# yBrainA1-11March2015.net
KiCad netlist of a schematic drawn in EAGLE
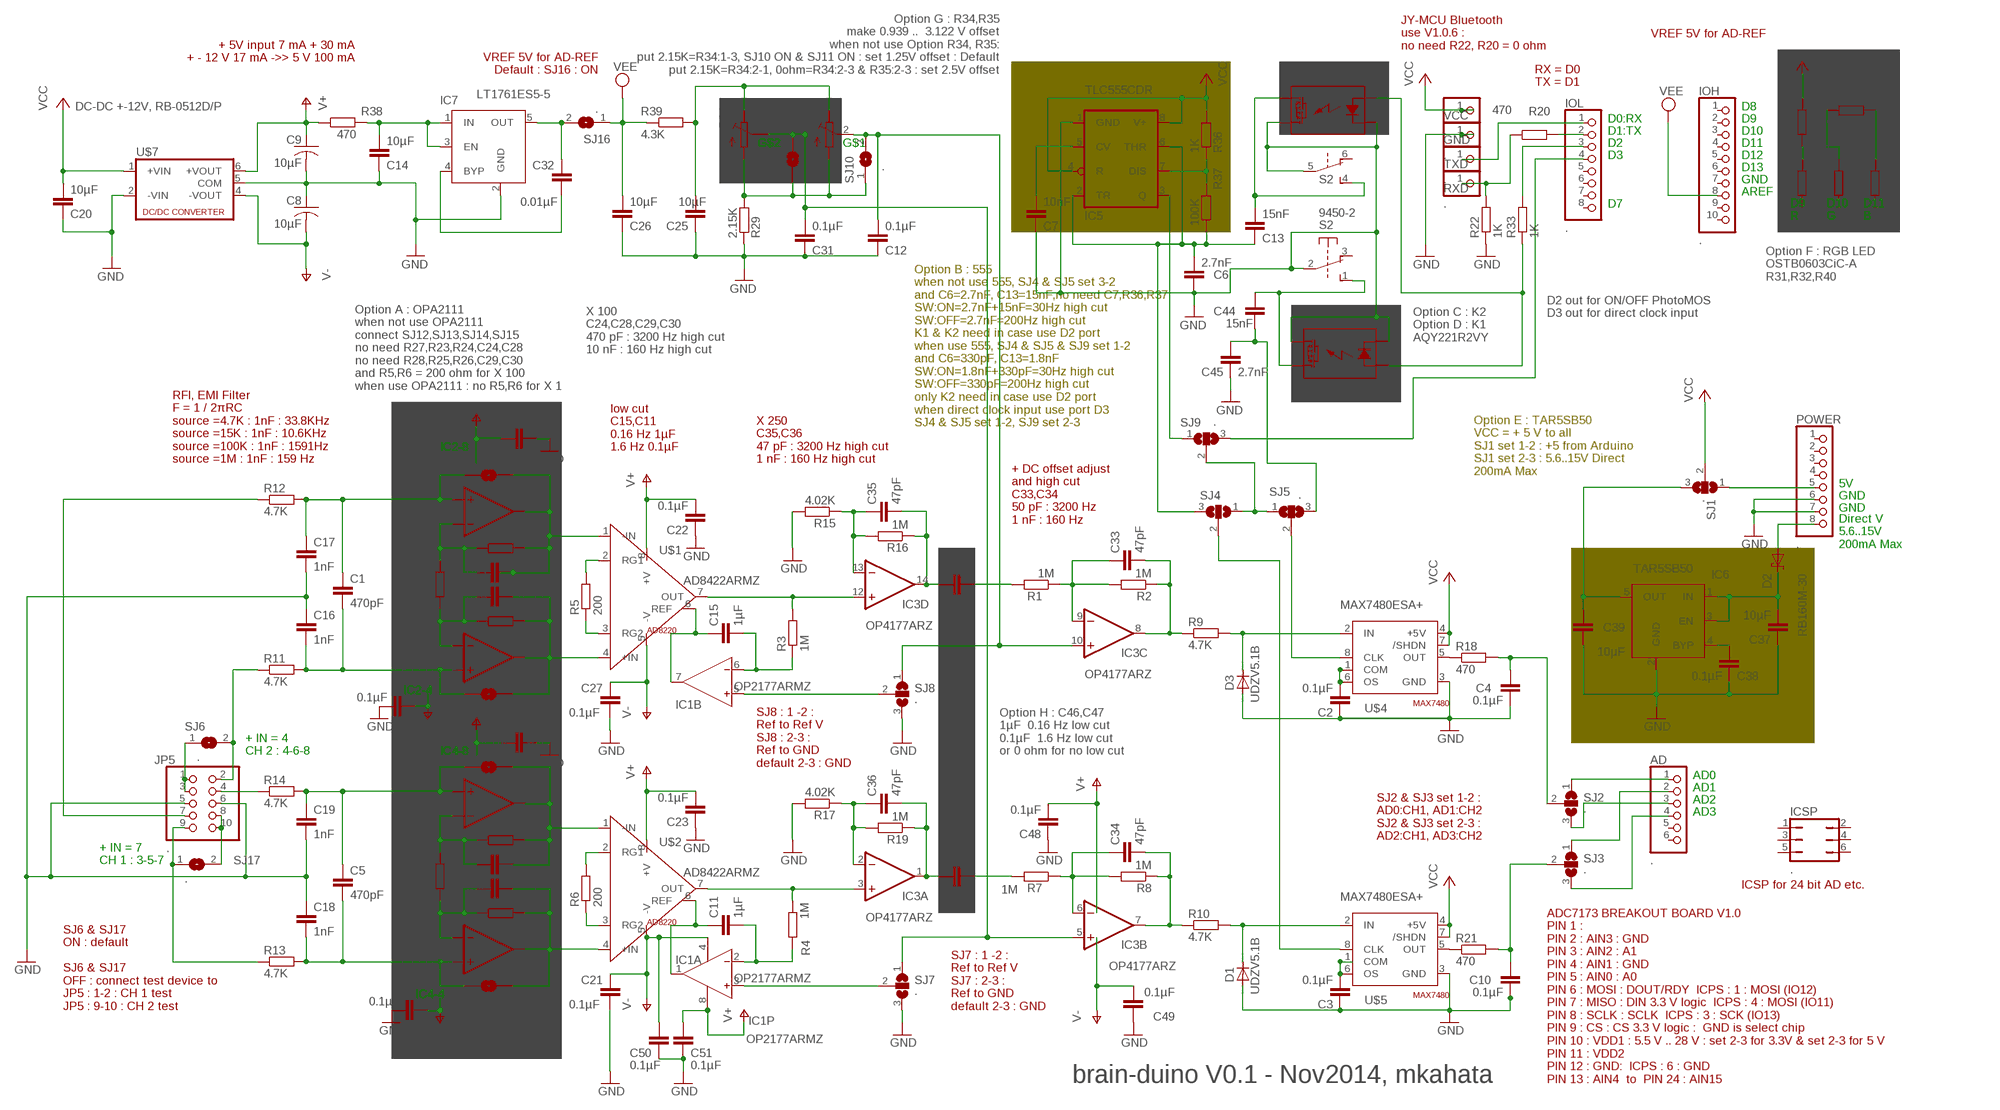
[diagram p0: schematic, sheet 1]

(export (version "E")
  (design (tool "Eeschema 10.0.6"))
  (components
    (comp (ref "AD")
      (value ".")
      (footprint "eagle-import:1X06")
      (libsource (lib "eagle-import") (part "PINHD-1X6"))
    )
    (comp (ref "C1")
      (value "470pF")
      (footprint "eagle-import:C0805")
      (libsource (lib "eagle-import") (part "C-EUC0805"))
    )
    (comp (ref "C2")
      (value "0.1µF")
      (footprint "eagle-import:C0805")
      (libsource (lib "eagle-import") (part "C-EUC0805"))
    )
    (comp (ref "C3")
      (value "0.1µF")
      (footprint "eagle-import:C0805")
      (libsource (lib "eagle-import") (part "C-EUC0805"))
    )
    (comp (ref "C4")
      (value "0.1µF")
      (footprint "eagle-import:C0805")
      (libsource (lib "eagle-import") (part "C-EUC0805"))
    )
    (comp (ref "C5")
      (value "470pF")
      (footprint "eagle-import:C0805")
      (libsource (lib "eagle-import") (part "C-EUC0805"))
    )
    (comp (ref "C6")
      (value "2.7nF")
      (footprint "eagle-import:C0805")
      (libsource (lib "eagle-import") (part "C-EUC0805"))
    )
    (comp (ref "C7")
      (value "10nF")
      (footprint "eagle-import:C0805")
      (libsource (lib "eagle-import") (part "C-EUC0805"))
    )
    (comp (ref "C8")
      (value "10µF")
      (footprint "eagle-import:C0805")
      (libsource (lib "eagle-import") (part "C-USC0805"))
    )
    (comp (ref "C9")
      (value "10µF")
      (footprint "eagle-import:C0805")
      (libsource (lib "eagle-import") (part "C-USC0805"))
    )
    (comp (ref "C10")
      (value "0.1µF")
      (footprint "eagle-import:C0805")
      (libsource (lib "eagle-import") (part "C-EUC0805"))
    )
    (comp (ref "C11")
      (value "1µF")
      (footprint "eagle-import:C0805")
      (libsource (lib "eagle-import") (part "C-EUC0805"))
    )
    (comp (ref "C12")
      (value "0.1µF")
      (footprint "eagle-import:C0805")
      (libsource (lib "eagle-import") (part "C-EUC0805"))
    )
    (comp (ref "C13")
      (value "15nF")
      (footprint "eagle-import:C0805")
      (libsource (lib "eagle-import") (part "C-EUC0805"))
    )
    (comp (ref "C14")
      (value "10µF")
      (footprint "eagle-import:C0805")
      (libsource (lib "eagle-import") (part "C-EUC0805"))
    )
    (comp (ref "C15")
      (value "1µF")
      (footprint "eagle-import:C0805")
      (libsource (lib "eagle-import") (part "C-EUC0805"))
    )
    (comp (ref "C16")
      (value "1nF")
      (footprint "eagle-import:C0805")
      (libsource (lib "eagle-import") (part "C-EUC0805"))
    )
    (comp (ref "C17")
      (value "1nF")
      (footprint "eagle-import:C0805")
      (libsource (lib "eagle-import") (part "C-EUC0805"))
    )
    (comp (ref "C18")
      (value "1nF")
      (footprint "eagle-import:C0805")
      (libsource (lib "eagle-import") (part "C-EUC0805"))
    )
    (comp (ref "C19")
      (value "1nF")
      (footprint "eagle-import:C0805")
      (libsource (lib "eagle-import") (part "C-EUC0805"))
    )
    (comp (ref "C20")
      (value "10µF")
      (footprint "eagle-import:C0805")
      (libsource (lib "eagle-import") (part "C-EUC0805"))
    )
    (comp (ref "C21")
      (value "0.1µF")
      (footprint "eagle-import:C0805")
      (libsource (lib "eagle-import") (part "C-EUC0805"))
    )
    (comp (ref "C22")
      (value "0.1µF")
      (footprint "eagle-import:C0805")
      (libsource (lib "eagle-import") (part "C-EUC0805"))
    )
    (comp (ref "C23")
      (value "0.1µF")
      (footprint "eagle-import:C0805")
      (libsource (lib "eagle-import") (part "C-EUC0805"))
    )
    (comp (ref "C24")
      (value "470pF")
      (footprint "eagle-import:C0805")
      (libsource (lib "eagle-import") (part "C-EUC0805"))
    )
    (comp (ref "C25")
      (value "10µF")
      (footprint "eagle-import:C0805")
      (libsource (lib "eagle-import") (part "C-EUC0805"))
    )
    (comp (ref "C26")
      (value "10µF")
      (footprint "eagle-import:C0805")
      (libsource (lib "eagle-import") (part "C-EUC0805"))
    )
    (comp (ref "C27")
      (value "0.1µF")
      (footprint "eagle-import:C0805")
      (libsource (lib "eagle-import") (part "C-EUC0805"))
    )
    (comp (ref "C28")
      (value "470pF")
      (footprint "eagle-import:C0805")
      (libsource (lib "eagle-import") (part "C-EUC0805"))
    )
    (comp (ref "C29")
      (value "470pF")
      (footprint "eagle-import:C0805")
      (libsource (lib "eagle-import") (part "C-EUC0805"))
    )
    (comp (ref "C30")
      (value "470pF")
      (footprint "eagle-import:C0805")
      (libsource (lib "eagle-import") (part "C-EUC0805"))
    )
    (comp (ref "C31")
      (value "0.1µF")
      (footprint "eagle-import:C0805")
      (libsource (lib "eagle-import") (part "C-EUC0805"))
    )
    (comp (ref "C32")
      (value "0.01µF")
      (footprint "eagle-import:C0805")
      (libsource (lib "eagle-import") (part "C-EUC0805"))
    )
    (comp (ref "C33")
      (value "47pF")
      (footprint "eagle-import:C0805")
      (libsource (lib "eagle-import") (part "C-EUC0805"))
    )
    (comp (ref "C34")
      (value "47pF")
      (footprint "eagle-import:C0805")
      (libsource (lib "eagle-import") (part "C-EUC0805"))
    )
    (comp (ref "C35")
      (value "47pF")
      (footprint "eagle-import:C0805")
      (libsource (lib "eagle-import") (part "C-EUC0805"))
    )
    (comp (ref "C36")
      (value "47pF")
      (footprint "eagle-import:C0805")
      (libsource (lib "eagle-import") (part "C-EUC0805"))
    )
    (comp (ref "C37")
      (value "10µF")
      (footprint "eagle-import:C0805")
      (libsource (lib "eagle-import") (part "C-EUC0805"))
    )
    (comp (ref "C38")
      (value "0.1µF")
      (footprint "eagle-import:C0805")
      (libsource (lib "eagle-import") (part "C-EUC0805"))
    )
    (comp (ref "C39")
      (value "10µF")
      (footprint "eagle-import:C0805")
      (libsource (lib "eagle-import") (part "C-EUC0805"))
    )
    (comp (ref "C40")
      (value "0.1µF")
      (footprint "eagle-import:C0805")
      (libsource (lib "eagle-import") (part "C-EUC0805"))
    )
    (comp (ref "C41")
      (value "0.1µF")
      (footprint "eagle-import:C0805")
      (libsource (lib "eagle-import") (part "C-EUC0805"))
    )
    (comp (ref "C42")
      (value "0.1µF")
      (footprint "eagle-import:C0805")
      (libsource (lib "eagle-import") (part "C-EUC0805"))
    )
    (comp (ref "C43")
      (value "0.1µF")
      (footprint "eagle-import:C0805")
      (libsource (lib "eagle-import") (part "C-EUC0805"))
    )
    (comp (ref "C44")
      (value "15nF")
      (footprint "eagle-import:C0805")
      (libsource (lib "eagle-import") (part "C-EUC0805"))
    )
    (comp (ref "C45")
      (value "2.7nF")
      (footprint "eagle-import:C0805")
      (libsource (lib "eagle-import") (part "C-EUC0805"))
    )
    (comp (ref "C46")
      (value "1µF")
      (footprint "eagle-import:C0805")
      (libsource (lib "eagle-import") (part "C-EUC0805"))
    )
    (comp (ref "C47")
      (value "1µF")
      (footprint "eagle-import:C0805")
      (libsource (lib "eagle-import") (part "C-EUC0805"))
    )
    (comp (ref "C48")
      (value "0.1µF")
      (footprint "eagle-import:C0805")
      (libsource (lib "eagle-import") (part "C-EUC0805"))
    )
    (comp (ref "C49")
      (value "0.1µF")
      (footprint "eagle-import:C0805")
      (libsource (lib "eagle-import") (part "C-EUC0805"))
    )
    (comp (ref "C50")
      (value "0.1µF")
      (footprint "eagle-import:C0805")
      (libsource (lib "eagle-import") (part "C-EUC0805"))
    )
    (comp (ref "C51")
      (value "0.1µF")
      (footprint "eagle-import:C0805")
      (libsource (lib "eagle-import") (part "C-EUC0805"))
    )
    (comp (ref "D1")
      (value "UDZV5.1B")
      (footprint "eagle-import:SOD110-R")
      (libsource (lib "eagle-import") (part "DIODE-SOD110-R"))
    )
    (comp (ref "D2")
      (value "RB160M-30")
      (footprint "eagle-import:POWERDI323")
      (libsource (lib "eagle-import") (part "PD3S160"))
    )
    (comp (ref "D3")
      (value "UDZV5.1B")
      (footprint "eagle-import:SOD110-R")
      (libsource (lib "eagle-import") (part "DIODE-SOD110-R"))
    )
    (comp (ref "GND")
      (value ".")
      (footprint "eagle-import:1X01")
      (libsource (lib "eagle-import") (part "PINHD-1X1"))
    )
    (comp (ref "IC1")
      (value "OP2177ARMZ")
      (footprint "eagle-import:MSOP08")
      (fields (field (name "MPN") "AD8656ARMZ"))
      (libsource (lib "eagle-import") (part "AD8656RM"))
    )
    (comp (ref "IC2")
      (value "OPA2111KP")
      (footprint "eagle-import:DIL08")
      (libsource (lib "eagle-import") (part "OPA2111P"))
    )
    (comp (ref "IC3")
      (value "OP4177ARZ")
      (footprint "eagle-import:SO14")
      (libsource (lib "eagle-import") (part "TL064D"))
    )
    (comp (ref "IC4")
      (value "OPA2111KP")
      (footprint "eagle-import:DIL08")
      (libsource (lib "eagle-import") (part "OPA2111P"))
    )
    (comp (ref "IC5")
      (value "TLC555CDR")
      (footprint "eagle-import:SO08")
      (libsource (lib "eagle-import") (part "555DLM"))
    )
    (comp (ref "IC6")
      (value "TAR5SB50")
      (footprint "eagle-import:SOT23-5")
      (libsource (lib "eagle-import") (part "MIC5219XX"))
    )
    (comp (ref "IC7")
      (value "LT1761ES5-5")
      (footprint "eagle-import:SOT23-5")
      (libsource (lib "eagle-import") (part "MIC5219XX"))
    )
    (comp (ref "ICSP")
      (value ".")
      (footprint "eagle-import:JP3Q")
      (libsource (lib "eagle-import") (part "JP3Q"))
    )
    (comp (ref "IOH")
      (value ".")
      (footprint "eagle-import:1X10")
      (libsource (lib "eagle-import") (part "PINHD-1X10"))
    )
    (comp (ref "IOL")
      (value ".")
      (footprint "eagle-import:1X08")
      (libsource (lib "eagle-import") (part "PINHD-1X8"))
    )
    (comp (ref "JP5")
      (value ".")
      (footprint "eagle-import:2X05_90")
      (libsource (lib "eagle-import") (part "PINHD-2X5/90"))
    )
    (comp (ref "K1")
      (value "AQY221R2VY")
      (footprint "eagle-import:SSOP4")
      (fields (field (name "MF") "AROMAT/ MATSUSHITA") (field (name "MPN") "AQY221R2V"))
      (libsource (lib "eagle-import") (part "AQY2212VR"))
    )
    (comp (ref "K2")
      (value "AQY221R2VY")
      (footprint "eagle-import:SSOP4")
      (fields (field (name "MF") "AROMAT/ MATSUSHITA") (field (name "MPN") "AQY221R2V"))
      (libsource (lib "eagle-import") (part "AQY2212VR"))
    )
    (comp (ref "POWER")
      (value ".")
      (footprint "eagle-import:1X08")
      (libsource (lib "eagle-import") (part "PINHD-1X8"))
    )
    (comp (ref "R1")
      (value "1M")
      (footprint "eagle-import:R0805")
      (libsource (lib "eagle-import") (part "R-EU_R0805"))
    )
    (comp (ref "R2")
      (value "1M")
      (footprint "eagle-import:R0805")
      (libsource (lib "eagle-import") (part "R-EU_R0805"))
    )
    (comp (ref "R3")
      (value "1M")
      (footprint "eagle-import:R0805")
      (libsource (lib "eagle-import") (part "R-EU_R0805"))
    )
    (comp (ref "R4")
      (value "1M")
      (footprint "eagle-import:R0805")
      (libsource (lib "eagle-import") (part "R-EU_R0805"))
    )
    (comp (ref "R5")
      (value "200")
      (footprint "eagle-import:R0805")
      (libsource (lib "eagle-import") (part "R-EU_R0805"))
    )
    (comp (ref "R6")
      (value "200")
      (footprint "eagle-import:R0805")
      (libsource (lib "eagle-import") (part "R-EU_R0805"))
    )
    (comp (ref "R7")
      (value "1M")
      (footprint "eagle-import:R0805")
      (libsource (lib "eagle-import") (part "R-EU_R0805"))
    )
    (comp (ref "R8")
      (value "1M")
      (footprint "eagle-import:R0805")
      (libsource (lib "eagle-import") (part "R-EU_R0805"))
    )
    (comp (ref "R9")
      (value "4.7K")
      (footprint "eagle-import:R0805")
      (libsource (lib "eagle-import") (part "R-EU_R0805"))
    )
    (comp (ref "R10")
      (value "4.7K")
      (footprint "eagle-import:R0805")
      (libsource (lib "eagle-import") (part "R-EU_R0805"))
    )
    (comp (ref "R11")
      (value "4.7K")
      (footprint "eagle-import:R0805")
      (libsource (lib "eagle-import") (part "R-EU_R0805"))
    )
    (comp (ref "R12")
      (value "4.7K")
      (footprint "eagle-import:R0805")
      (libsource (lib "eagle-import") (part "R-EU_R0805"))
    )
    (comp (ref "R13")
      (value "4.7K")
      (footprint "eagle-import:R0805")
      (libsource (lib "eagle-import") (part "R-EU_R0805"))
    )
    (comp (ref "R14")
      (value "4.7K")
      (footprint "eagle-import:R0805")
      (libsource (lib "eagle-import") (part "R-EU_R0805"))
    )
    (comp (ref "R15")
      (value "4.02K")
      (footprint "eagle-import:R0805")
      (libsource (lib "eagle-import") (part "R-EU_R0805"))
    )
    (comp (ref "R16")
      (value "1M")
      (footprint "eagle-import:R0805")
      (libsource (lib "eagle-import") (part "R-EU_R0805"))
    )
    (comp (ref "R17")
      (value "4.02K")
      (footprint "eagle-import:R0805")
      (libsource (lib "eagle-import") (part "R-EU_R0805"))
    )
    (comp (ref "R18")
      (value "470")
      (footprint "eagle-import:R0805")
      (libsource (lib "eagle-import") (part "R-EU_R0805"))
    )
    (comp (ref "R19")
      (value "1M")
      (footprint "eagle-import:R0805")
      (libsource (lib "eagle-import") (part "R-EU_R0805"))
    )
    (comp (ref "R20")
      (value "470")
      (footprint "eagle-import:R0805")
      (libsource (lib "eagle-import") (part "R-EU_R0805"))
    )
    (comp (ref "R21")
      (value "470")
      (footprint "eagle-import:R0805")
      (libsource (lib "eagle-import") (part "R-EU_R0805"))
    )
    (comp (ref "R22")
      (value "1K")
      (footprint "eagle-import:R0805")
      (libsource (lib "eagle-import") (part "R-EU_R0805"))
    )
    (comp (ref "R23")
      (value "100K")
      (footprint "eagle-import:R0805")
      (libsource (lib "eagle-import") (part "R-EU_R0805"))
    )
    (comp (ref "R24")
      (value "100K")
      (footprint "eagle-import:R0805")
      (libsource (lib "eagle-import") (part "R-EU_R0805"))
    )
    (comp (ref "R25")
      (value "100K")
      (footprint "eagle-import:R0805")
      (libsource (lib "eagle-import") (part "R-EU_R0805"))
    )
    (comp (ref "R26")
      (value "100K")
      (footprint "eagle-import:R0805")
      (libsource (lib "eagle-import") (part "R-EU_R0805"))
    )
    (comp (ref "R27")
      (value "2K")
      (footprint "eagle-import:R0805")
      (libsource (lib "eagle-import") (part "R-EU_R0805"))
    )
    (comp (ref "R28")
      (value "2K")
      (footprint "eagle-import:R0805")
      (libsource (lib "eagle-import") (part "R-EU_R0805"))
    )
    (comp (ref "R29")
      (value "2.15K")
      (footprint "eagle-import:R0805")
      (libsource (lib "eagle-import") (part "R-EU_R0805"))
    )
    (comp (ref "R30")
      (value "LED")
      (footprint "eagle-import:R0402")
      (libsource (lib "eagle-import") (part "R-EU_R0402"))
    )
    (comp (ref "R31")
      (value "1K")
      (footprint "eagle-import:R0402")
      (libsource (lib "eagle-import") (part "R-EU_R0402"))
    )
    (comp (ref "R32")
      (value "1K")
      (footprint "eagle-import:R0402")
      (libsource (lib "eagle-import") (part "R-EU_R0402"))
    )
    (comp (ref "R33")
      (value "1K")
      (footprint "eagle-import:R0805")
      (libsource (lib "eagle-import") (part "R-EU_R0805"))
    )
    (comp (ref "R34")
      (value "10K")
      (footprint "eagle-import:RTRIM5X")
      (libsource (lib "eagle-import") (part "R-TRIMM5X"))
    )
    (comp (ref "R35")
      (value "10K")
      (footprint "eagle-import:RTRIM5X")
      (libsource (lib "eagle-import") (part "R-TRIMM5X"))
    )
    (comp (ref "R36")
      (value "1K")
      (footprint "eagle-import:R0805")
      (libsource (lib "eagle-import") (part "R-EU_R0805"))
    )
    (comp (ref "R37")
      (value "100K")
      (footprint "eagle-import:R0805")
      (libsource (lib "eagle-import") (part "R-EU_R0805"))
    )
    (comp (ref "R38")
      (value "470")
      (footprint "eagle-import:R0805")
      (libsource (lib "eagle-import") (part "R-EU_R0805"))
    )
    (comp (ref "R39")
      (value "4.3K")
      (footprint "eagle-import:R0805")
      (libsource (lib "eagle-import") (part "R-EU_R0805"))
    )
    (comp (ref "R40")
      (value "1K")
      (footprint "eagle-import:R0402")
      (libsource (lib "eagle-import") (part "R-EU_R0402"))
    )
    (comp (ref "R41")
      (value "LED")
      (footprint "eagle-import:R0402")
      (libsource (lib "eagle-import") (part "R-EU_R0402"))
    )
    (comp (ref "RXD")
      (value ".")
      (footprint "eagle-import:1X01")
      (libsource (lib "eagle-import") (part "PINHD-1X1"))
    )
    (comp (ref "S2")
      (value "9450-2")
      (footprint "eagle-import:9450-2")
      (libsource (lib "eagle-import") (part "9450-2"))
    )
    (comp (ref "SJ1")
      (value ".")
      (footprint "eagle-import:SJ_2")
      (libsource (lib "eagle-import") (part "SJ2W"))
    )
    (comp (ref "SJ2")
      (value ".")
      (footprint "eagle-import:SJ_2")
      (libsource (lib "eagle-import") (part "SJ2W"))
    )
    (comp (ref "SJ3")
      (value ".")
      (footprint "eagle-import:SJ_2")
      (libsource (lib "eagle-import") (part "SJ2W"))
    )
    (comp (ref "SJ4")
      (value ".")
      (footprint "eagle-import:SJ_2")
      (libsource (lib "eagle-import") (part "SJ2W"))
    )
    (comp (ref "SJ5")
      (value ".")
      (footprint "eagle-import:SJ_2")
      (libsource (lib "eagle-import") (part "SJ2W"))
    )
    (comp (ref "SJ6") (value ".") (footprint "eagle-import:SJ") (libsource (lib "eagle-import") (part "SJ")))
    (comp (ref "SJ7")
      (value ".")
      (footprint "eagle-import:SJ_2")
      (libsource (lib "eagle-import") (part "SJ2W"))
    )
    (comp (ref "SJ8")
      (value ".")
      (footprint "eagle-import:SJ_2")
      (libsource (lib "eagle-import") (part "SJ2W"))
    )
    (comp (ref "SJ9")
      (value ".")
      (footprint "eagle-import:SJ_2")
      (libsource (lib "eagle-import") (part "SJ2W"))
    )
    (comp (ref "SJ10") (value ".") (footprint "eagle-import:SJ") (libsource (lib "eagle-import") (part "SJ")))
    (comp (ref "SJ11") (value ".") (footprint "eagle-import:SJ") (libsource (lib "eagle-import") (part "SJ")))
    (comp (ref "SJ12") (value ".") (footprint "eagle-import:SJ") (libsource (lib "eagle-import") (part "SJ")))
    (comp (ref "SJ13") (value ".") (footprint "eagle-import:SJ") (libsource (lib "eagle-import") (part "SJ")))
    (comp (ref "SJ14") (value ".") (footprint "eagle-import:SJ") (libsource (lib "eagle-import") (part "SJ")))
    (comp (ref "SJ15") (value ".") (footprint "eagle-import:SJ") (libsource (lib "eagle-import") (part "SJ")))
    (comp (ref "SJ16") (value ".") (footprint "eagle-import:SJ") (libsource (lib "eagle-import") (part "SJ")))
    (comp (ref "SJ17") (value ".") (footprint "eagle-import:SJ") (libsource (lib "eagle-import") (part "SJ")))
    (comp (ref "TXD")
      (value ".")
      (footprint "eagle-import:1X01")
      (libsource (lib "eagle-import") (part "PINHD-1X1"))
    )
    (comp (ref "U$1")
      (value "AD8422ARMZ")
      (footprint "eagle-import:AD8220")
      (libsource (lib "eagle-import") (part "AD8220"))
    )
    (comp (ref "U$2")
      (value "AD8422ARMZ")
      (footprint "eagle-import:AD8220")
      (libsource (lib "eagle-import") (part "AD8220"))
    )
    (comp (ref "U$4")
      (value "MAX7480ESA+")
      (footprint "eagle-import:MAX7480")
      (libsource (lib "eagle-import") (part "MAX7480"))
    )
    (comp (ref "U$5")
      (value "MAX7480ESA+")
      (footprint "eagle-import:MAX7480")
      (libsource (lib "eagle-import") (part "MAX7480"))
    )
    (comp (ref "U$7")
      (value "DC-DC +-12V, RB-0512D/P")
      (footprint "eagle-import:RB-0515D")
      (libsource (lib "eagle-import") (part "RB-0515D"))
    )
    (comp (ref "VCC")
      (value ".")
      (footprint "eagle-import:1X01")
      (libsource (lib "eagle-import") (part "PINHD-1X1"))
    )
  )
  (nets
    (net (code "1") (name "GND") (class "Default")
      (node (ref "C10") (pin "1") (pinfunction "1_1") (pintype "passive"))
      (node (ref "C12") (pin "1") (pinfunction "1_1") (pintype "passive"))
      (node (ref "C14") (pin "1") (pinfunction "1_1") (pintype "passive"))
      (node (ref "C16") (pin "1") (pinfunction "1_1") (pintype "passive"))
      (node (ref "C17") (pin "2") (pinfunction "2_2") (pintype "passive"))
      (node (ref "C18") (pin "1") (pinfunction "1_1") (pintype "passive"))
      (node (ref "C19") (pin "2") (pinfunction "2_2") (pintype "passive"))
      (node (ref "C2") (pin "1") (pinfunction "1_1") (pintype "passive"))
      (node (ref "C20") (pin "1") (pinfunction "1_1") (pintype "passive"))
      (node (ref "C21") (pin "2") (pinfunction "2_2") (pintype "passive"))
      (node (ref "C22") (pin "1") (pinfunction "1_1") (pintype "passive"))
      (node (ref "C23") (pin "1") (pinfunction "1_1") (pintype "passive"))
      (node (ref "C25") (pin "1") (pinfunction "1_1") (pintype "passive"))
      (node (ref "C26") (pin "1") (pinfunction "1_1") (pintype "passive"))
      (node (ref "C27") (pin "2") (pinfunction "2_2") (pintype "passive"))
      (node (ref "C3") (pin "1") (pinfunction "1_1") (pintype "passive"))
      (node (ref "C31") (pin "1") (pinfunction "1_1") (pintype "passive"))
      (node (ref "C37") (pin "1") (pinfunction "1_1") (pintype "passive"))
      (node (ref "C38") (pin "1") (pinfunction "1_1") (pintype "passive"))
      (node (ref "C39") (pin "1") (pinfunction "1_1") (pintype "passive"))
      (node (ref "C4") (pin "1") (pinfunction "1_1") (pintype "passive"))
      (node (ref "C40") (pin "1") (pinfunction "1_1") (pintype "passive"))
      (node (ref "C41") (pin "2") (pinfunction "2_2") (pintype "passive"))
      (node (ref "C42") (pin "2") (pinfunction "2_2") (pintype "passive"))
      (node (ref "C43") (pin "2") (pinfunction "2_2") (pintype "passive"))
      (node (ref "C45") (pin "1") (pinfunction "1_1") (pintype "passive"))
      (node (ref "C48") (pin "1") (pinfunction "1_1") (pintype "passive"))
      (node (ref "C49") (pin "1") (pinfunction "1_1") (pintype "passive"))
      (node (ref "C50") (pin "2") (pinfunction "2_2") (pintype "passive"))
      (node (ref "C51") (pin "2") (pinfunction "2_2") (pintype "passive"))
      (node (ref "C6") (pin "1") (pinfunction "1_1") (pintype "passive"))
      (node (ref "C7") (pin "1") (pinfunction "1_1") (pintype "passive"))
      (node (ref "C8") (pin "1") (pinfunction "1_1") (pintype "passive"))
      (node (ref "C9") (pin "2") (pinfunction "2_2") (pintype "passive"))
      (node (ref "D1") (pin "A") (pinfunction "A_A") (pintype "passive"))
      (node (ref "D3") (pin "A") (pinfunction "A_A") (pintype "passive"))
      (node (ref "GND") (pin "1") (pinfunction "1_1") (pintype "passive"))
      (node (ref "IC5") (pin "1") (pinfunction "GND_1") (pintype "power_in"))
      (node (ref "IC6") (pin "2") (pinfunction "GND_2") (pintype "power_in"))
      (node (ref "IC7") (pin "2") (pinfunction "GND_2") (pintype "power_in"))
      (node (ref "JP5") (pin "5") (pinfunction "5_5") (pintype "passive"))
      (node (ref "JP5") (pin "6") (pinfunction "6_6") (pintype "passive"))
      (node (ref "K1") (pin "2") (pinfunction "K_2") (pintype "passive"))
      (node (ref "K1") (pin "3") (pinfunction "DS2_3") (pintype "passive"))
      (node (ref "K2") (pin "2") (pinfunction "K_2") (pintype "passive"))
      (node (ref "K2") (pin "3") (pinfunction "DS2_3") (pintype "passive"))
      (node (ref "POWER") (pin "6") (pinfunction "6_6") (pintype "passive"))
      (node (ref "POWER") (pin "7") (pinfunction "7_7") (pintype "passive"))
      (node (ref "R15") (pin "2") (pinfunction "2_2") (pintype "passive"))
      (node (ref "R17") (pin "2") (pinfunction "2_2") (pintype "passive"))
      (node (ref "R22") (pin "1") (pinfunction "1_1") (pintype "passive"))
      (node (ref "R29") (pin "1") (pinfunction "1_1") (pintype "passive"))
      (node (ref "S2") (pin "2") (pinfunction "P_2") (pintype "passive"))
      (node (ref "S2") (pin "5") (pinfunction "P_5") (pintype "passive"))
      (node (ref "SJ7") (pin "3") (pinfunction "3_3") (pintype "passive"))
      (node (ref "SJ8") (pin "3") (pinfunction "3_3") (pintype "passive"))
      (node (ref "U$4") (pin "3") (pinfunction "GND_3") (pintype "power_in"))
      (node (ref "U$5") (pin "3") (pinfunction "GND_3") (pintype "power_in"))
      (node (ref "U$7") (pin "2") (pinfunction "-VIN_2") (pintype "passive"))
      (node (ref "U$7") (pin "5") (pinfunction "COM_5") (pintype "passive"))
    )
    (net (code "2") (name "Net-(AD-Pad1)") (class "Default")
      (node (ref "AD") (pin "1") (pinfunction "1_1") (pintype "passive"))
      (node (ref "SJ2") (pin "1") (pinfunction "1_1") (pintype "passive"))
    )
    (net (code "3") (name "Net-(AD-Pad2)") (class "Default")
      (node (ref "AD") (pin "2") (pinfunction "2_2") (pintype "passive"))
      (node (ref "SJ3") (pin "1") (pinfunction "1_1") (pintype "passive"))
    )
    (net (code "4") (name "Net-(AD-Pad3)") (class "Default")
      (node (ref "AD") (pin "3") (pinfunction "3_3") (pintype "passive"))
      (node (ref "SJ2") (pin "3") (pinfunction "3_3") (pintype "passive"))
    )
    (net (code "5") (name "Net-(AD-Pad4)") (class "Default")
      (node (ref "AD") (pin "4") (pinfunction "4_4") (pintype "passive"))
      (node (ref "SJ3") (pin "3") (pinfunction "3_3") (pintype "passive"))
    )
    (net (code "6") (name "Net-(C4-Pad2)") (class "Default")
      (node (ref "C4") (pin "2") (pinfunction "2_2") (pintype "passive"))
      (node (ref "R18") (pin "2") (pinfunction "2_2") (pintype "passive"))
      (node (ref "SJ2") (pin "2") (pinfunction "2_2") (pintype "passive"))
    )
    (net (code "7") (name "Net-(C10-Pad2)") (class "Default")
      (node (ref "C10") (pin "2") (pinfunction "2_2") (pintype "passive"))
      (node (ref "R21") (pin "2") (pinfunction "2_2") (pintype "passive"))
      (node (ref "SJ3") (pin "2") (pinfunction "2_2") (pintype "passive"))
    )
    (net (code "8") (name "Net-(C44-Pad1)") (class "Default")
      (node (ref "C44") (pin "1") (pinfunction "1_1") (pintype "passive"))
      (node (ref "C45") (pin "2") (pinfunction "2_2") (pintype "passive"))
      (node (ref "SJ5") (pin "3") (pinfunction "3_3") (pintype "passive"))
    )
    (net (code "9") (name "Net-(C46-Pad2)") (class "Default")
      (node (ref "C46") (pin "2") (pinfunction "2_2") (pintype "passive"))
      (node (ref "R1") (pin "2") (pinfunction "2_2") (pintype "passive"))
    )
    (net (code "10") (name "Net-(C47-Pad2)") (class "Default")
      (node (ref "C47") (pin "2") (pinfunction "2_2") (pintype "passive"))
      (node (ref "R7") (pin "2") (pinfunction "2_2") (pintype "passive"))
    )
    (net (code "11") (name "Net-(D2-PadA)") (class "Default")
      (node (ref "D2") (pin "A") (pinfunction "A_A") (pintype "passive"))
      (node (ref "POWER") (pin "8") (pinfunction "8_8") (pintype "passive"))
    )
    (net (code "12") (name "Net-(IC1A-IN+)") (class "Default")
      (node (ref "IC1") (pin "3") (pinfunction "IN+_3") (pintype "input"))
      (node (ref "SJ7") (pin "2") (pinfunction "2_2") (pintype "passive"))
    )
    (net (code "13") (name "Net-(IC1A-IN-)") (class "Default")
      (node (ref "C11") (pin "2") (pinfunction "2_2") (pintype "passive"))
      (node (ref "IC1") (pin "2") (pinfunction "IN-_2") (pintype "input"))
      (node (ref "R4") (pin "1") (pinfunction "1_1") (pintype "passive"))
    )
    (net (code "14") (name "Net-(IC1A-OUT)") (class "Default")
      (node (ref "C11") (pin "1") (pinfunction "1_1") (pintype "passive"))
      (node (ref "IC1") (pin "1") (pinfunction "OUT_1") (pintype "output"))
      (node (ref "U$2") (pin "6") (pinfunction "REF_6") (pintype "input"))
    )
    (net (code "15") (name "Net-(IC1B-IN+)") (class "Default")
      (node (ref "IC1") (pin "5") (pinfunction "IN+_5") (pintype "input"))
      (node (ref "SJ8") (pin "2") (pinfunction "2_2") (pintype "passive"))
    )
    (net (code "16") (name "Net-(IC1B-IN-)") (class "Default")
      (node (ref "C15") (pin "2") (pinfunction "2_2") (pintype "passive"))
      (node (ref "IC1") (pin "6") (pinfunction "IN-_6") (pintype "input"))
      (node (ref "R3") (pin "1") (pinfunction "1_1") (pintype "passive"))
    )
    (net (code "17") (name "Net-(IC1B-OUT)") (class "Default")
      (node (ref "C15") (pin "1") (pinfunction "1_1") (pintype "passive"))
      (node (ref "IC1") (pin "7") (pinfunction "OUT_7") (pintype "output"))
      (node (ref "U$1") (pin "6") (pinfunction "REF_6") (pintype "input"))
    )
    (net (code "18") (name "Net-(IC2A-+IN)") (class "Default")
      (node (ref "C1") (pin "1") (pinfunction "1_1") (pintype "passive"))
      (node (ref "C17") (pin "1") (pinfunction "1_1") (pintype "passive"))
      (node (ref "IC2") (pin "3") (pinfunction "+IN_3") (pintype "input"))
      (node (ref "R12") (pin "2") (pinfunction "2_2") (pintype "passive"))
      (node (ref "SJ12") (pin "2") (pinfunction "2_2") (pintype "passive"))
    )
    (net (code "19") (name "Net-(IC2A--IN)") (class "Default")
      (node (ref "C24") (pin "1") (pinfunction "1_1") (pintype "passive"))
      (node (ref "IC2") (pin "2") (pinfunction "-IN_2") (pintype "input"))
      (node (ref "R23") (pin "1") (pinfunction "1_1") (pintype "passive"))
      (node (ref "R27") (pin "2") (pinfunction "2_2") (pintype "passive"))
    )
    (net (code "20") (name "Net-(IC2A-OUT)") (class "Default")
      (node (ref "C24") (pin "2") (pinfunction "2_2") (pintype "passive"))
      (node (ref "IC2") (pin "1") (pinfunction "OUT_1") (pintype "output"))
      (node (ref "R23") (pin "2") (pinfunction "2_2") (pintype "passive"))
      (node (ref "SJ12") (pin "1") (pinfunction "1_1") (pintype "passive"))
      (node (ref "U$1") (pin "1") (pinfunction "-IN_1") (pintype "input"))
    )
    (net (code "21") (name "Net-(IC2B-+IN)") (class "Default")
      (node (ref "C1") (pin "2") (pinfunction "2_2") (pintype "passive"))
      (node (ref "C16") (pin "2") (pinfunction "2_2") (pintype "passive"))
      (node (ref "IC2") (pin "5") (pinfunction "+IN_5") (pintype "input"))
      (node (ref "R11") (pin "2") (pinfunction "2_2") (pintype "passive"))
      (node (ref "SJ13") (pin "2") (pinfunction "2_2") (pintype "passive"))
    )
    (net (code "22") (name "Net-(IC2B--IN)") (class "Default")
      (node (ref "C28") (pin "1") (pinfunction "1_1") (pintype "passive"))
      (node (ref "IC2") (pin "6") (pinfunction "-IN_6") (pintype "input"))
      (node (ref "R24") (pin "1") (pinfunction "1_1") (pintype "passive"))
      (node (ref "R27") (pin "1") (pinfunction "1_1") (pintype "passive"))
    )
    (net (code "23") (name "Net-(IC2B-OUT)") (class "Default")
      (node (ref "C28") (pin "2") (pinfunction "2_2") (pintype "passive"))
      (node (ref "IC2") (pin "7") (pinfunction "OUT_7") (pintype "output"))
      (node (ref "R24") (pin "2") (pinfunction "2_2") (pintype "passive"))
      (node (ref "SJ13") (pin "1") (pinfunction "1_1") (pintype "passive"))
      (node (ref "U$1") (pin "4") (pinfunction "+IN_4") (pintype "passive"))
    )
    (net (code "24") (name "Net-(IC3A-+IN)") (class "Default")
      (node (ref "IC3") (pin "3") (pinfunction "+IN_3") (pintype "input"))
      (node (ref "R4") (pin "2") (pinfunction "2_2") (pintype "passive"))
      (node (ref "U$2") (pin "7") (pinfunction "OUT_7") (pintype "input"))
    )
    (net (code "25") (name "Net-(IC3A--IN)") (class "Default")
      (node (ref "C36") (pin "1") (pinfunction "1_1") (pintype "passive"))
      (node (ref "IC3") (pin "2") (pinfunction "-IN_2") (pintype "input"))
      (node (ref "R17") (pin "1") (pinfunction "1_1") (pintype "passive"))
      (node (ref "R19") (pin "2") (pinfunction "2_2") (pintype "passive"))
    )
    (net (code "26") (name "Net-(IC3A-OUT)") (class "Default")
      (node (ref "C36") (pin "2") (pinfunction "2_2") (pintype "passive"))
      (node (ref "C47") (pin "1") (pinfunction "1_1") (pintype "passive"))
      (node (ref "IC3") (pin "1") (pinfunction "OUT_1") (pintype "output"))
      (node (ref "R19") (pin "1") (pinfunction "1_1") (pintype "passive"))
    )
    (net (code "27") (name "Net-(IC3B-+IN)") (class "Default")
      (node (ref "C31") (pin "2") (pinfunction "2_2") (pintype "passive"))
      (node (ref "IC3") (pin "5") (pinfunction "+IN_5") (pintype "input"))
      (node (ref "R34") (pin "2") (pinfunction "S_2") (pintype "passive"))
      (node (ref "SJ11") (pin "2") (pinfunction "2_2") (pintype "passive"))
      (node (ref "SJ7") (pin "1") (pinfunction "1_1") (pintype "passive"))
    )
    (net (code "28") (name "Net-(IC3B--IN)") (class "Default")
      (node (ref "C34") (pin "1") (pinfunction "1_1") (pintype "passive"))
      (node (ref "IC3") (pin "6") (pinfunction "-IN_6") (pintype "input"))
      (node (ref "R7") (pin "1") (pinfunction "1_1") (pintype "passive"))
      (node (ref "R8") (pin "2") (pinfunction "2_2") (pintype "passive"))
    )
    (net (code "29") (name "Net-(IC3B-OUT)") (class "Default")
      (node (ref "C34") (pin "2") (pinfunction "2_2") (pintype "passive"))
      (node (ref "IC3") (pin "7") (pinfunction "OUT_7") (pintype "output"))
      (node (ref "R10") (pin "1") (pinfunction "1_1") (pintype "passive"))
      (node (ref "R8") (pin "1") (pinfunction "1_1") (pintype "passive"))
    )
    (net (code "30") (name "Net-(IC3C-+IN)") (class "Default")
      (node (ref "C12") (pin "2") (pinfunction "2_2") (pintype "passive"))
      (node (ref "IC3") (pin "10") (pinfunction "+IN_10") (pintype "input"))
      (node (ref "R35") (pin "2") (pinfunction "S_2") (pintype "passive"))
      (node (ref "SJ10") (pin "2") (pinfunction "2_2") (pintype "passive"))
      (node (ref "SJ8") (pin "1") (pinfunction "1_1") (pintype "passive"))
    )
    (net (code "31") (name "Net-(IC3C--IN)") (class "Default")
      (node (ref "C33") (pin "1") (pinfunction "1_1") (pintype "passive"))
      (node (ref "IC3") (pin "9") (pinfunction "-IN_9") (pintype "input"))
      (node (ref "R1") (pin "1") (pinfunction "1_1") (pintype "passive"))
      (node (ref "R2") (pin "2") (pinfunction "2_2") (pintype "passive"))
    )
    (net (code "32") (name "Net-(IC3C-OUT)") (class "Default")
      (node (ref "C33") (pin "2") (pinfunction "2_2") (pintype "passive"))
      (node (ref "IC3") (pin "8") (pinfunction "OUT_8") (pintype "output"))
      (node (ref "R2") (pin "1") (pinfunction "1_1") (pintype "passive"))
      (node (ref "R9") (pin "1") (pinfunction "1_1") (pintype "passive"))
    )
    (net (code "33") (name "Net-(IC3D-+IN)") (class "Default")
      (node (ref "IC3") (pin "12") (pinfunction "+IN_12") (pintype "input"))
      (node (ref "R3") (pin "2") (pinfunction "2_2") (pintype "passive"))
      (node (ref "U$1") (pin "7") (pinfunction "OUT_7") (pintype "input"))
    )
    (net (code "34") (name "Net-(IC3D--IN)") (class "Default")
      (node (ref "C35") (pin "1") (pinfunction "1_1") (pintype "passive"))
      (node (ref "IC3") (pin "13") (pinfunction "-IN_13") (pintype "input"))
      (node (ref "R15") (pin "1") (pinfunction "1_1") (pintype "passive"))
      (node (ref "R16") (pin "2") (pinfunction "2_2") (pintype "passive"))
    )
    (net (code "35") (name "Net-(IC3D-OUT)") (class "Default")
      (node (ref "C35") (pin "2") (pinfunction "2_2") (pintype "passive"))
      (node (ref "C46") (pin "1") (pinfunction "1_1") (pintype "passive"))
      (node (ref "IC3") (pin "14") (pinfunction "OUT_14") (pintype "output"))
      (node (ref "R16") (pin "1") (pinfunction "1_1") (pintype "passive"))
    )
    (net (code "36") (name "Net-(IC4A-+IN)") (class "Default")
      (node (ref "C19") (pin "1") (pinfunction "1_1") (pintype "passive"))
      (node (ref "C5") (pin "1") (pinfunction "1_1") (pintype "passive"))
      (node (ref "IC4") (pin "3") (pinfunction "+IN_3") (pintype "input"))
      (node (ref "R14") (pin "2") (pinfunction "2_2") (pintype "passive"))
      (node (ref "SJ14") (pin "2") (pinfunction "2_2") (pintype "passive"))
    )
    (net (code "37") (name "Net-(IC4A--IN)") (class "Default")
      (node (ref "C29") (pin "1") (pinfunction "1_1") (pintype "passive"))
      (node (ref "IC4") (pin "2") (pinfunction "-IN_2") (pintype "input"))
      (node (ref "R25") (pin "1") (pinfunction "1_1") (pintype "passive"))
      (node (ref "R28") (pin "2") (pinfunction "2_2") (pintype "passive"))
    )
    (net (code "38") (name "Net-(IC4A-OUT)") (class "Default")
      (node (ref "C29") (pin "2") (pinfunction "2_2") (pintype "passive"))
      (node (ref "IC4") (pin "1") (pinfunction "OUT_1") (pintype "output"))
      (node (ref "R25") (pin "2") (pinfunction "2_2") (pintype "passive"))
      (node (ref "SJ14") (pin "1") (pinfunction "1_1") (pintype "passive"))
      (node (ref "U$2") (pin "1") (pinfunction "-IN_1") (pintype "input"))
    )
    (net (code "39") (name "Net-(IC4B-+IN)") (class "Default")
      (node (ref "C18") (pin "2") (pinfunction "2_2") (pintype "passive"))
      (node (ref "C5") (pin "2") (pinfunction "2_2") (pintype "passive"))
      (node (ref "IC4") (pin "5") (pinfunction "+IN_5") (pintype "input"))
      (node (ref "R13") (pin "2") (pinfunction "2_2") (pintype "passive"))
      (node (ref "SJ15") (pin "2") (pinfunction "2_2") (pintype "passive"))
    )
    (net (code "40") (name "Net-(IC4B--IN)") (class "Default")
      (node (ref "C30") (pin "1") (pinfunction "1_1") (pintype "passive"))
      (node (ref "IC4") (pin "6") (pinfunction "-IN_6") (pintype "input"))
      (node (ref "R26") (pin "1") (pinfunction "1_1") (pintype "passive"))
      (node (ref "R28") (pin "1") (pinfunction "1_1") (pintype "passive"))
    )
    (net (code "41") (name "Net-(IC4B-OUT)") (class "Default")
      (node (ref "C30") (pin "2") (pinfunction "2_2") (pintype "passive"))
      (node (ref "IC4") (pin "7") (pinfunction "OUT_7") (pintype "output"))
      (node (ref "R26") (pin "2") (pinfunction "2_2") (pintype "passive"))
      (node (ref "SJ15") (pin "1") (pinfunction "1_1") (pintype "passive"))
      (node (ref "U$2") (pin "4") (pinfunction "+IN_4") (pintype "passive"))
    )
    (net (code "42") (name "Net-(IC5-CV)") (class "Default")
      (node (ref "C7") (pin "2") (pinfunction "2_2") (pintype "passive"))
      (node (ref "IC5") (pin "5") (pinfunction "CV_5") (pintype "input"))
    )
    (net (code "43") (name "Net-(IC5-DIS)") (class "Default")
      (node (ref "IC5") (pin "7") (pinfunction "DIS_7") (pintype "input"))
      (node (ref "R36") (pin "1") (pinfunction "1_1") (pintype "passive"))
      (node (ref "R37") (pin "2") (pinfunction "2_2") (pintype "passive"))
    )
    (net (code "44") (name "Net-(IC5-Q)") (class "Default")
      (node (ref "IC5") (pin "3") (pinfunction "Q_3") (pintype "output"))
      (node (ref "SJ9") (pin "1") (pinfunction "1_1") (pintype "passive"))
    )
    (net (code "45") (name "Net-(IC5-THR)") (class "Default")
      (node (ref "C13") (pin "1") (pinfunction "1_1") (pintype "passive"))
      (node (ref "C6") (pin "2") (pinfunction "2_2") (pintype "passive"))
      (node (ref "IC5") (pin "2") (pinfunction "TR_2") (pintype "input"))
      (node (ref "IC5") (pin "6") (pinfunction "THR_6") (pintype "input"))
      (node (ref "R37") (pin "1") (pinfunction "1_1") (pintype "passive"))
      (node (ref "SJ4") (pin "3") (pinfunction "3_3") (pintype "passive"))
    )
    (net (code "46") (name "Net-(IC6-BYP)") (class "Default")
      (node (ref "C38") (pin "2") (pinfunction "2_2") (pintype "passive"))
      (node (ref "IC6") (pin "4") (pinfunction "BYP_4") (pintype "passive"))
    )
    (net (code "47") (name "Net-(IC6-EN)") (class "Default")
      (node (ref "C37") (pin "2") (pinfunction "2_2") (pintype "passive"))
      (node (ref "D2") (pin "C") (pinfunction "C_C") (pintype "passive"))
      (node (ref "IC6") (pin "1") (pinfunction "IN_1") (pintype "input"))
      (node (ref "IC6") (pin "3") (pinfunction "EN_3") (pintype "input"))
    )
    (net (code "48") (name "Net-(IC6-OUT)") (class "Default")
      (node (ref "C39") (pin "2") (pinfunction "2_2") (pintype "passive"))
      (node (ref "IC6") (pin "5") (pinfunction "OUT_5") (pintype "output"))
      (node (ref "SJ1") (pin "3") (pinfunction "3_3") (pintype "passive"))
    )
    (net (code "49") (name "Net-(IC7-BYP)") (class "Default")
      (node (ref "C32") (pin "1") (pinfunction "1_1") (pintype "passive"))
      (node (ref "IC7") (pin "4") (pinfunction "BYP_4") (pintype "passive"))
    )
    (net (code "50") (name "Net-(IC7-EN)") (class "Default")
      (node (ref "C14") (pin "2") (pinfunction "2_2") (pintype "passive"))
      (node (ref "IC7") (pin "1") (pinfunction "IN_1") (pintype "input"))
      (node (ref "IC7") (pin "3") (pinfunction "EN_3") (pintype "input"))
      (node (ref "R38") (pin "2") (pinfunction "2_2") (pintype "passive"))
    )
    (net (code "51") (name "Net-(IC7-OUT)") (class "Default")
      (node (ref "C32") (pin "2") (pinfunction "2_2") (pintype "passive"))
      (node (ref "IC7") (pin "5") (pinfunction "OUT_5") (pintype "output"))
      (node (ref "SJ16") (pin "2") (pinfunction "2_2") (pintype "passive"))
    )
    (net (code "52") (name "Net-(IOL-Pad1)") (class "Default")
      (node (ref "IOL") (pin "1") (pinfunction "1_1") (pintype "passive"))
      (node (ref "TXD") (pin "1") (pinfunction "1_1") (pintype "passive"))
    )
    (net (code "53") (name "Net-(IOL-Pad2)") (class "Default")
      (node (ref "IOL") (pin "2") (pinfunction "2_2") (pintype "passive"))
      (node (ref "R20") (pin "2") (pinfunction "2_2") (pintype "passive"))
    )
    (net (code "54") (name "Net-(IOL-Pad3)") (class "Default")
      (node (ref "IOL") (pin "3") (pinfunction "3_3") (pintype "passive"))
      (node (ref "R33") (pin "2") (pinfunction "2_2") (pintype "passive"))
    )
    (net (code "55") (name "Net-(IOL-Pad4)") (class "Default")
      (node (ref "IOL") (pin "4") (pinfunction "4_4") (pintype "passive"))
      (node (ref "SJ9") (pin "3") (pinfunction "3_3") (pintype "passive"))
    )
    (net (code "56") (name "Net-(JP5-Pad1)") (class "Default")
      (node (ref "JP5") (pin "1") (pinfunction "1_1") (pintype "passive"))
      (node (ref "JP5") (pin "3") (pinfunction "3_3") (pintype "passive"))
      (node (ref "SJ6") (pin "1") (pinfunction "1_1") (pintype "passive"))
    )
    (net (code "57") (name "Net-(JP5-Pad2)") (class "Default")
      (node (ref "JP5") (pin "2") (pinfunction "2_2") (pintype "passive"))
      (node (ref "R11") (pin "1") (pinfunction "1_1") (pintype "passive"))
      (node (ref "SJ6") (pin "2") (pinfunction "2_2") (pintype "passive"))
    )
    (net (code "58") (name "Net-(JP5-Pad4)") (class "Default")
      (node (ref "JP5") (pin "4") (pinfunction "4_4") (pintype "passive"))
      (node (ref "R14") (pin "1") (pinfunction "1_1") (pintype "passive"))
    )
    (net (code "59") (name "Net-(JP5-Pad7)") (class "Default")
      (node (ref "JP5") (pin "7") (pinfunction "7_7") (pintype "passive"))
      (node (ref "R12") (pin "1") (pinfunction "1_1") (pintype "passive"))
    )
    (net (code "60") (name "Net-(JP5-Pad9)") (class "Default")
      (node (ref "JP5") (pin "9") (pinfunction "9_9") (pintype "passive"))
      (node (ref "R13") (pin "1") (pinfunction "1_1") (pintype "passive"))
      (node (ref "SJ17") (pin "1") (pinfunction "1_1") (pintype "passive"))
    )
    (net (code "61") (name "Net-(JP5-Pad10)") (class "Default")
      (node (ref "JP5") (pin "10") (pinfunction "10_10") (pintype "passive"))
      (node (ref "JP5") (pin "8") (pinfunction "8_8") (pintype "passive"))
      (node (ref "SJ17") (pin "2") (pinfunction "2_2") (pintype "passive"))
    )
    (net (code "62") (name "Net-(K1-A)") (class "Default")
      (node (ref "K1") (pin "1") (pinfunction "A_1") (pintype "passive"))
      (node (ref "K2") (pin "1") (pinfunction "A_1") (pintype "passive"))
      (node (ref "R33") (pin "1") (pinfunction "1_1") (pintype "passive"))
    )
    (net (code "63") (name "Net-(K1-DS1)") (class "Default")
      (node (ref "C44") (pin "2") (pinfunction "2_2") (pintype "passive"))
      (node (ref "K1") (pin "4") (pinfunction "DS1_4") (pintype "passive"))
      (node (ref "S2") (pin "1") (pinfunction "S_1") (pintype "passive"))
    )
    (net (code "64") (name "Net-(K2-DS1)") (class "Default")
      (node (ref "C13") (pin "2") (pinfunction "2_2") (pintype "passive"))
      (node (ref "K2") (pin "4") (pinfunction "DS1_4") (pintype "passive"))
      (node (ref "S2") (pin "4") (pinfunction "S_4") (pintype "passive"))
    )
    (net (code "65") (name "Net-(POWER-Pad5)") (class "Default")
      (node (ref "POWER") (pin "5") (pinfunction "5_5") (pintype "passive"))
      (node (ref "SJ1") (pin "1") (pinfunction "1_1") (pintype "passive"))
    )
    (net (code "66") (name "Net-(R20-Pad1)") (class "Default")
      (node (ref "R20") (pin "1") (pinfunction "1_1") (pintype "passive"))
      (node (ref "R22") (pin "2") (pinfunction "2_2") (pintype "passive"))
      (node (ref "RXD") (pin "1") (pinfunction "1_1") (pintype "passive"))
    )
    (net (code "67") (name "Net-(R30-Pad1)") (class "Default")
      (node (ref "R30") (pin "1") (pinfunction "1_1") (pintype "passive"))
      (node (ref "R40") (pin "2") (pinfunction "2_2") (pintype "passive"))
    )
    (net (code "68") (name "Net-(R30-Pad2)") (class "Default")
      (node (ref "R30") (pin "2") (pinfunction "2_2") (pintype "passive"))
      (node (ref "R32") (pin "2") (pinfunction "2_2") (pintype "passive"))
    )
    (net (code "69") (name "Net-(R31-Pad2)") (class "Default")
      (node (ref "R31") (pin "2") (pinfunction "2_2") (pintype "passive"))
      (node (ref "R41") (pin "1") (pinfunction "1_1") (pintype "passive"))
    )
    (net (code "70") (name "Net-(R34-A)") (class "Default")
      (node (ref "C25") (pin "2") (pinfunction "2_2") (pintype "passive"))
      (node (ref "R34") (pin "3") (pinfunction "A_3") (pintype "passive"))
      (node (ref "R35") (pin "3") (pinfunction "A_3") (pintype "passive"))
      (node (ref "R39") (pin "2") (pinfunction "2_2") (pintype "passive"))
    )
    (net (code "71") (name "Net-(R34-E)") (class "Default")
      (node (ref "R29") (pin "2") (pinfunction "2_2") (pintype "passive"))
      (node (ref "R34") (pin "1") (pinfunction "E_1") (pintype "passive"))
      (node (ref "R35") (pin "1") (pinfunction "E_1") (pintype "passive"))
      (node (ref "SJ10") (pin "1") (pinfunction "1_1") (pintype "passive"))
      (node (ref "SJ11") (pin "1") (pinfunction "1_1") (pintype "passive"))
    )
    (net (code "72") (name "Net-(SJ4-Pad1)") (class "Default")
      (node (ref "SJ4") (pin "1") (pinfunction "1_1") (pintype "passive"))
      (node (ref "SJ5") (pin "1") (pinfunction "1_1") (pintype "passive"))
      (node (ref "SJ9") (pin "2") (pinfunction "2_2") (pintype "passive"))
    )
    (net (code "73") (name "Net-(U$1-RG1)") (class "Default")
      (node (ref "R5") (pin "2") (pinfunction "2_2") (pintype "passive"))
      (node (ref "U$1") (pin "2") (pinfunction "RG1_2") (pintype "input"))
    )
    (net (code "74") (name "Net-(U$1-RG2)") (class "Default")
      (node (ref "R5") (pin "1") (pinfunction "1_1") (pintype "passive"))
      (node (ref "U$1") (pin "3") (pinfunction "RG2_3") (pintype "input"))
    )
    (net (code "75") (name "Net-(U$2-RG1)") (class "Default")
      (node (ref "R6") (pin "2") (pinfunction "2_2") (pintype "passive"))
      (node (ref "U$2") (pin "2") (pinfunction "RG1_2") (pintype "input"))
    )
    (net (code "76") (name "Net-(U$2-RG2)") (class "Default")
      (node (ref "R6") (pin "1") (pinfunction "1_1") (pintype "passive"))
      (node (ref "U$2") (pin "3") (pinfunction "RG2_3") (pintype "input"))
    )
    (net (code "77") (name "Net-(U$4-CLK)") (class "Default")
      (node (ref "SJ5") (pin "2") (pinfunction "2_2") (pintype "passive"))
      (node (ref "U$4") (pin "8") (pinfunction "CLK_8") (pintype "input"))
    )
    (net (code "78") (name "Net-(U$4-COM)") (class "Default")
      (node (ref "C2") (pin "2") (pinfunction "2_2") (pintype "passive"))
      (node (ref "U$4") (pin "1") (pinfunction "COM_1") (pintype "input"))
      (node (ref "U$4") (pin "6") (pinfunction "OS_6") (pintype "passive"))
    )
    (net (code "79") (name "Net-(U$4-IN)") (class "Default")
      (node (ref "D3") (pin "C") (pinfunction "C_C") (pintype "passive"))
      (node (ref "R9") (pin "2") (pinfunction "2_2") (pintype "passive"))
      (node (ref "U$4") (pin "2") (pinfunction "IN_2") (pintype "input"))
    )
    (net (code "80") (name "Net-(U$4-OUT)") (class "Default")
      (node (ref "R18") (pin "1") (pinfunction "1_1") (pintype "passive"))
      (node (ref "U$4") (pin "5") (pinfunction "OUT_5") (pintype "input"))
    )
    (net (code "81") (name "Net-(U$5-CLK)") (class "Default")
      (node (ref "SJ4") (pin "2") (pinfunction "2_2") (pintype "passive"))
      (node (ref "U$5") (pin "8") (pinfunction "CLK_8") (pintype "input"))
    )
    (net (code "82") (name "Net-(U$5-COM)") (class "Default")
      (node (ref "C3") (pin "2") (pinfunction "2_2") (pintype "passive"))
      (node (ref "U$5") (pin "1") (pinfunction "COM_1") (pintype "input"))
      (node (ref "U$5") (pin "6") (pinfunction "OS_6") (pintype "passive"))
    )
    (net (code "83") (name "Net-(U$5-IN)") (class "Default")
      (node (ref "D1") (pin "C") (pinfunction "C_C") (pintype "passive"))
      (node (ref "R10") (pin "2") (pinfunction "2_2") (pintype "passive"))
      (node (ref "U$5") (pin "2") (pinfunction "IN_2") (pintype "input"))
    )
    (net (code "84") (name "Net-(U$5-OUT)") (class "Default")
      (node (ref "R21") (pin "1") (pinfunction "1_1") (pintype "passive"))
      (node (ref "U$5") (pin "5") (pinfunction "OUT_5") (pintype "input"))
    )
    (net (code "85") (name "V+") (class "Default")
      (node (ref "C22") (pin "2") (pinfunction "2_2") (pintype "passive"))
      (node (ref "C23") (pin "2") (pinfunction "2_2") (pintype "passive"))
      (node (ref "C40") (pin "2") (pinfunction "2_2") (pintype "passive"))
      (node (ref "C42") (pin "1") (pinfunction "1_1") (pintype "passive"))
      (node (ref "C48") (pin "2") (pinfunction "2_2") (pintype "passive"))
      (node (ref "C51") (pin "1") (pinfunction "1_1") (pintype "passive"))
      (node (ref "C9") (pin "1") (pinfunction "1_1") (pintype "passive"))
      (node (ref "IC1") (pin "8") (pinfunction "V+_8") (pintype "power_in"))
      (node (ref "R38") (pin "1") (pinfunction "1_1") (pintype "passive"))
      (node (ref "U$1") (pin "8") (pinfunction "+V_8") (pintype "power_in"))
      (node (ref "U$2") (pin "8") (pinfunction "+V_8") (pintype "power_in"))
      (node (ref "U$7") (pin "6") (pinfunction "+VOUT_6") (pintype "passive"))
    )
    (net (code "86") (name "V-") (class "Default")
      (node (ref "C21") (pin "1") (pinfunction "1_1") (pintype "passive"))
      (node (ref "C27") (pin "1") (pinfunction "1_1") (pintype "passive"))
      (node (ref "C41") (pin "1") (pinfunction "1_1") (pintype "passive"))
      (node (ref "C43") (pin "1") (pinfunction "1_1") (pintype "passive"))
      (node (ref "C49") (pin "2") (pinfunction "2_2") (pintype "passive"))
      (node (ref "C50") (pin "1") (pinfunction "1_1") (pintype "passive"))
      (node (ref "C8") (pin "2") (pinfunction "2_2") (pintype "passive"))
      (node (ref "IC1") (pin "4") (pinfunction "V-_4") (pintype "power_in"))
      (node (ref "U$1") (pin "5") (pinfunction "-V_5") (pintype "power_in"))
      (node (ref "U$2") (pin "5") (pinfunction "-V_5") (pintype "power_in"))
      (node (ref "U$7") (pin "4") (pinfunction "-VOUT_4") (pintype "passive"))
    )
    (net (code "87") (name "VCC") (class "Default")
      (node (ref "C20") (pin "2") (pinfunction "2_2") (pintype "passive"))
      (node (ref "IC5") (pin "4") (pinfunction "R_4") (pintype "input"))
      (node (ref "IC5") (pin "8") (pinfunction "V+_8") (pintype "power_in"))
      (node (ref "R36") (pin "2") (pinfunction "2_2") (pintype "passive"))
      (node (ref "R41") (pin "2") (pinfunction "2_2") (pintype "passive"))
      (node (ref "SJ1") (pin "2") (pinfunction "2_2") (pintype "passive"))
      (node (ref "U$4") (pin "4") (pinfunction "+5V_4") (pintype "power_in"))
      (node (ref "U$4") (pin "7") (pinfunction "/SHDN_7") (pintype "input"))
      (node (ref "U$5") (pin "4") (pinfunction "+5V_4") (pintype "power_in"))
      (node (ref "U$5") (pin "7") (pinfunction "/SHDN_7") (pintype "input"))
      (node (ref "U$7") (pin "1") (pinfunction "+VIN_1") (pintype "passive"))
      (node (ref "VCC") (pin "1") (pinfunction "1_1") (pintype "passive"))
    )
    (net (code "88") (name "VEE") (class "Default")
      (node (ref "C26") (pin "2") (pinfunction "2_2") (pintype "passive"))
      (node (ref "IOH") (pin "8") (pinfunction "8_8") (pintype "passive"))
      (node (ref "R39") (pin "1") (pinfunction "1_1") (pintype "passive"))
      (node (ref "SJ16") (pin "1") (pinfunction "1_1") (pintype "passive"))
    )
    (net (code "89") (name "unconnected-(AD-Pad5)") (class "Default")
      (node (ref "AD") (pin "5") (pinfunction "5_5") (pintype "passive"))
    )
    (net (code "90") (name "unconnected-(AD-Pad6)") (class "Default")
      (node (ref "AD") (pin "6") (pinfunction "6_6") (pintype "passive"))
    )
    (net (code "91") (name "unconnected-(ICSP-Pad1)") (class "Default")
      (node (ref "ICSP") (pin "1") (pinfunction "1_1") (pintype "passive"))
    )
    (net (code "92") (name "unconnected-(ICSP-Pad2)") (class "Default")
      (node (ref "ICSP") (pin "2") (pinfunction "2_2") (pintype "passive"))
    )
    (net (code "93") (name "unconnected-(ICSP-Pad3)") (class "Default")
      (node (ref "ICSP") (pin "3") (pinfunction "3_3") (pintype "passive"))
    )
    (net (code "94") (name "unconnected-(ICSP-Pad4)") (class "Default")
      (node (ref "ICSP") (pin "4") (pinfunction "4_4") (pintype "passive"))
    )
    (net (code "95") (name "unconnected-(ICSP-Pad5)") (class "Default")
      (node (ref "ICSP") (pin "5") (pinfunction "5_5") (pintype "passive"))
    )
    (net (code "96") (name "unconnected-(ICSP-Pad6)") (class "Default")
      (node (ref "ICSP") (pin "6") (pinfunction "6_6") (pintype "passive"))
    )
    (net (code "97") (name "unconnected-(IOH-Pad1)") (class "Default")
      (node (ref "IOH") (pin "1") (pinfunction "1_1") (pintype "passive"))
    )
    (net (code "98") (name "unconnected-(IOH-Pad2)") (class "Default")
      (node (ref "IOH") (pin "2") (pinfunction "2_2") (pintype "passive"))
    )
    (net (code "99") (name "unconnected-(IOH-Pad3)") (class "Default")
      (node (ref "IOH") (pin "3") (pinfunction "3_3") (pintype "passive"))
    )
    (net (code "100") (name "unconnected-(IOH-Pad4)") (class "Default")
      (node (ref "IOH") (pin "4") (pinfunction "4_4") (pintype "passive"))
    )
    (net (code "101") (name "unconnected-(IOH-Pad5)") (class "Default")
      (node (ref "IOH") (pin "5") (pinfunction "5_5") (pintype "passive"))
    )
    (net (code "102") (name "unconnected-(IOH-Pad6)") (class "Default")
      (node (ref "IOH") (pin "6") (pinfunction "6_6") (pintype "passive"))
    )
    (net (code "103") (name "unconnected-(IOH-Pad7)") (class "Default")
      (node (ref "IOH") (pin "7") (pinfunction "7_7") (pintype "passive"))
    )
    (net (code "104") (name "unconnected-(IOH-Pad9)") (class "Default")
      (node (ref "IOH") (pin "9") (pinfunction "9_9") (pintype "passive"))
    )
    (net (code "105") (name "unconnected-(IOH-Pad10)") (class "Default")
      (node (ref "IOH") (pin "10") (pinfunction "10_10") (pintype "passive"))
    )
    (net (code "106") (name "unconnected-(IOL-Pad5)") (class "Default")
      (node (ref "IOL") (pin "5") (pinfunction "5_5") (pintype "passive"))
    )
    (net (code "107") (name "unconnected-(IOL-Pad6)") (class "Default")
      (node (ref "IOL") (pin "6") (pinfunction "6_6") (pintype "passive"))
    )
    (net (code "108") (name "unconnected-(IOL-Pad7)") (class "Default")
      (node (ref "IOL") (pin "7") (pinfunction "7_7") (pintype "passive"))
    )
    (net (code "109") (name "unconnected-(IOL-Pad8)") (class "Default")
      (node (ref "IOL") (pin "8") (pinfunction "8_8") (pintype "passive"))
    )
    (net (code "110") (name "unconnected-(POWER-Pad1)") (class "Default")
      (node (ref "POWER") (pin "1") (pinfunction "1_1") (pintype "passive"))
    )
    (net (code "111") (name "unconnected-(POWER-Pad2)") (class "Default")
      (node (ref "POWER") (pin "2") (pinfunction "2_2") (pintype "passive"))
    )
    (net (code "112") (name "unconnected-(POWER-Pad3)") (class "Default")
      (node (ref "POWER") (pin "3") (pinfunction "3_3") (pintype "passive"))
    )
    (net (code "113") (name "unconnected-(POWER-Pad4)") (class "Default")
      (node (ref "POWER") (pin "4") (pinfunction "4_4") (pintype "passive"))
    )
    (net (code "114") (name "unconnected-(R31-Pad1)") (class "Default")
      (node (ref "R31") (pin "1") (pinfunction "1_1") (pintype "passive"))
    )
    (net (code "115") (name "unconnected-(R32-Pad1)") (class "Default")
      (node (ref "R32") (pin "1") (pinfunction "1_1") (pintype "passive"))
    )
    (net (code "116") (name "unconnected-(R40-Pad1)") (class "Default")
      (node (ref "R40") (pin "1") (pinfunction "1_1") (pintype "passive"))
    )
    (net (code "117") (name "unconnected-(S2A-O-Pad3)") (class "Default")
      (node (ref "S2") (pin "3") (pinfunction "O_3") (pintype "passive"))
    )
    (net (code "118") (name "unconnected-(S2B-O-Pad6)") (class "Default")
      (node (ref "S2") (pin "6") (pinfunction "O_6") (pintype "passive"))
    )
  )
)
